# HB-OU-MP3-LED_V1_1.net
KiCad netlist of a schematic drawn in EAGLE
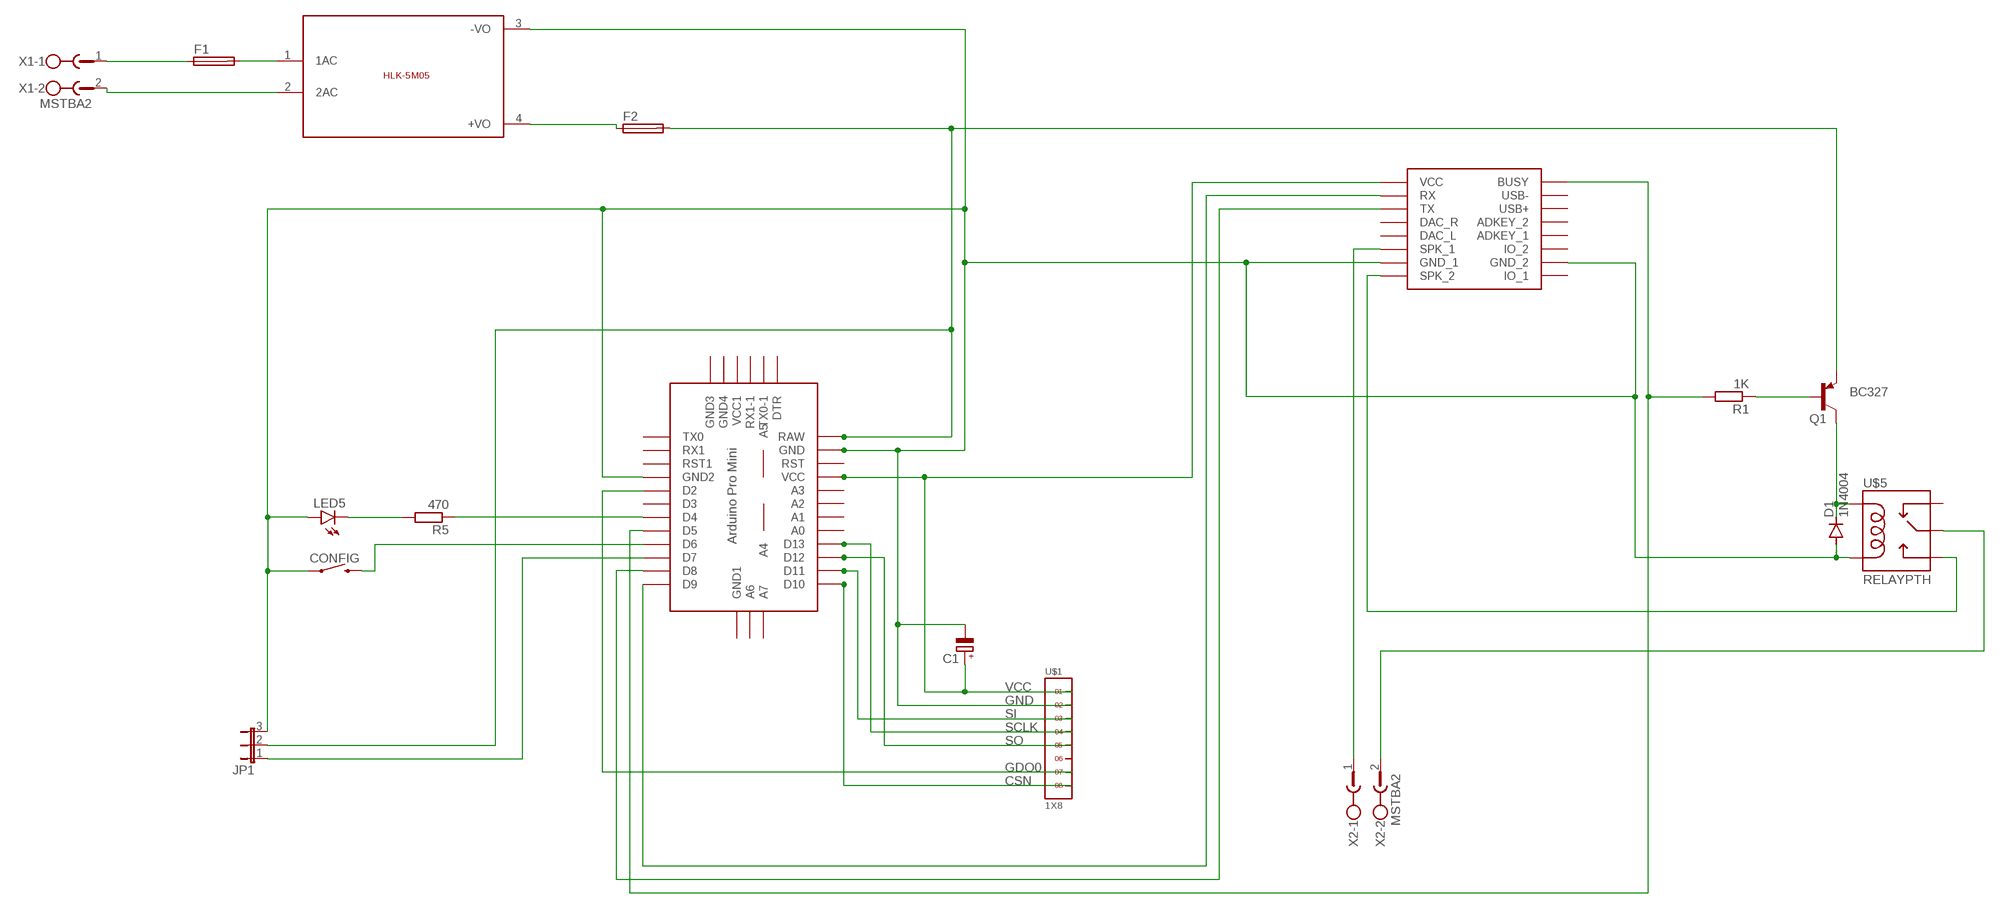
[diagram p0: schematic, sheet 1]

(export (version "E")
  (design (tool "Eeschema 10.0.6"))
  (components
    (comp (ref "C1")
      (value "CPOL-EUE2.5-5")
      (footprint "eagle-import:E2,5-5")
      (libsource (lib "eagle-import") (part "CPOL-EUE2.5-5"))
    )
    (comp (ref "CONFIG")
      (value "MOMENTARY-SWITCH-SPST-PTH-6.0MM-KIT")
      (footprint "eagle-import:TACTILE_SWITCH_PTH_6.0MM_KIT")
      (libsource (lib "eagle-import") (part "MOMENTARY-SWITCH-SPST-PTH-6.0MM-KIT"))
    )
    (comp (ref "D1")
      (value "1N4004")
      (footprint "eagle-import:DO41-10")
      (libsource (lib "eagle-import") (part "1N4004"))
    )
    (comp (ref "F1")
      (value "SH22,5A")
      (footprint "eagle-import:SH22,5A")
      (fields (field (name "MPN") "0031.7701.11"))
      (libsource (lib "eagle-import") (part "SH22,5A"))
    )
    (comp (ref "F2")
      (value "SH22,5A")
      (footprint "eagle-import:SH22,5A")
      (fields (field (name "MPN") "0031.7701.11"))
      (libsource (lib "eagle-import") (part "SH22,5A"))
    )
    (comp (ref "JP1")
      (value "JP2E")
      (footprint "eagle-import:JP2")
      (libsource (lib "eagle-import") (part "JP2E"))
    )
    (comp (ref "LED5")
      (value "LED3MM")
      (footprint "eagle-import:LED3MM")
      (libsource (lib "eagle-import") (part "LED3MM"))
    )
    (comp (ref "Q1")
      (value "BC327")
      (footprint "eagle-import:TO92")
      (libsource (lib "eagle-import") (part "BC327"))
    )
    (comp (ref "R1")
      (value "1K")
      (footprint "eagle-import:0309_10")
      (libsource (lib "eagle-import") (part "R-EU_0309/10"))
    )
    (comp (ref "R5")
      (value "470")
      (footprint "eagle-import:0309_10")
      (libsource (lib "eagle-import") (part "R-EU_0309/10"))
    )
    (comp (ref "U$1")
      (value "1X8")
      (footprint "eagle-import:1X8")
      (libsource (lib "eagle-import") (part "1X8"))
    )
    (comp (ref "U$2")
      (value "ABK-PRO-MINI")
      (footprint "eagle-import:ABK-PRO-MINI")
      (libsource (lib "eagle-import") (part "ABK-PRO-MINI"))
    )
    (comp (ref "U$3")
      (value "5VDC/5W")
      (footprint "eagle-import:HLK-5M05")
      (libsource (lib "eagle-import") (part "HLK-5M05"))
    )
    (comp (ref "U$4")
      (value "DFPLAYER")
      (footprint "eagle-import:DFPLAYER")
      (libsource (lib "eagle-import") (part "DFPLAYER"))
    )
    (comp (ref "U$5")
      (value "RELAYPTH")
      (footprint "eagle-import:SRD-05VDC-SL-C")
      (libsource (lib "eagle-import") (part "RELAYPTH"))
    )
    (comp (ref "X1")
      (value "MSTBA2")
      (footprint "eagle-import:MSTBA2")
      (fields (field (name "MF") "FARNELL") (field (name "MPN") "1757242"))
      (libsource (lib "eagle-import") (part "MSTBA2"))
    )
    (comp (ref "X2")
      (value "MSTBA2")
      (footprint "eagle-import:MSTBA2")
      (fields (field (name "MF") "FARNELL") (field (name "MPN") "1757242"))
      (libsource (lib "eagle-import") (part "MSTBA2"))
    )
  )
  (nets
    (net (code "1") (name "/CSN") (class "Default")
      (node (ref "U$1") (pin "8") (pinfunction "8_8") (pintype "bidirectional"))
      (node (ref "U$2") (pin "D10") (pinfunction "D10_D10") (pintype "bidirectional"))
    )
    (net (code "2") (name "/GDO0") (class "Default")
      (node (ref "U$1") (pin "7") (pinfunction "7_7") (pintype "bidirectional"))
      (node (ref "U$2") (pin "D2") (pinfunction "D2_D2") (pintype "bidirectional"))
    )
    (net (code "3") (name "/GND") (class "Default")
      (node (ref "C1") (pin "-") (pinfunction "-_-") (pintype "passive"))
      (node (ref "CONFIG") (pin "1") (pinfunction "1_1") (pintype "passive"))
      (node (ref "D1") (pin "A") (pinfunction "A_A") (pintype "passive"))
      (node (ref "JP1") (pin "3") (pinfunction "3_3") (pintype "passive"))
      (node (ref "LED5") (pin "A") (pinfunction "A_A") (pintype "passive"))
      (node (ref "U$1") (pin "2") (pinfunction "2_2") (pintype "bidirectional"))
      (node (ref "U$2") (pin "GND") (pinfunction "GND_GND") (pintype "bidirectional"))
      (node (ref "U$2") (pin "GND1") (pinfunction "GND2_GND1") (pintype "bidirectional"))
      (node (ref "U$3") (pin "3") (pinfunction "-VO_3") (pintype "bidirectional"))
      (node (ref "U$4") (pin "GND_1") (pinfunction "GND_1_GND_1") (pintype "bidirectional"))
      (node (ref "U$4") (pin "GND_2") (pinfunction "GND_2_GND_2") (pintype "bidirectional"))
      (node (ref "U$5") (pin "COIL0") (pinfunction "COIL0_COIL0") (pintype "bidirectional"))
    )
    (net (code "4") (name "/SCLK") (class "Default")
      (node (ref "U$1") (pin "4") (pinfunction "4_4") (pintype "bidirectional"))
      (node (ref "U$2") (pin "D13") (pinfunction "D13_D13") (pintype "bidirectional"))
    )
    (net (code "5") (name "/SI") (class "Default")
      (node (ref "U$1") (pin "3") (pinfunction "3_3") (pintype "bidirectional"))
      (node (ref "U$2") (pin "D11") (pinfunction "D11_D11") (pintype "bidirectional"))
    )
    (net (code "6") (name "/SO") (class "Default")
      (node (ref "U$1") (pin "5") (pinfunction "5_5") (pintype "bidirectional"))
      (node (ref "U$2") (pin "D12") (pinfunction "D12_D12") (pintype "bidirectional"))
    )
    (net (code "7") (name "/VCC") (class "Default")
      (node (ref "C1") (pin "+") (pinfunction "+_+") (pintype "passive"))
      (node (ref "U$1") (pin "1") (pinfunction "1_1") (pintype "bidirectional"))
      (node (ref "U$2") (pin "VCC") (pinfunction "VCC_VCC") (pintype "bidirectional"))
      (node (ref "U$4") (pin "VCC") (pinfunction "VCC_VCC") (pintype "bidirectional"))
    )
    (net (code "8") (name "Net-(CONFIG-2)") (class "Default")
      (node (ref "CONFIG") (pin "3") (pinfunction "2_3") (pintype "passive"))
      (node (ref "U$2") (pin "D6") (pinfunction "D6_D6") (pintype "bidirectional"))
    )
    (net (code "9") (name "Net-(F1-Pad1)") (class "Default")
      (node (ref "F1") (pin "1") (pinfunction "1_1") (pintype "passive"))
      (node (ref "X1") (pin "1") (pinfunction "1_1") (pintype "passive"))
    )
    (net (code "10") (name "Net-(JP1-Pad1)") (class "Default")
      (node (ref "JP1") (pin "1") (pinfunction "1_1") (pintype "passive"))
      (node (ref "U$2") (pin "D7") (pinfunction "D7_D7") (pintype "bidirectional"))
    )
    (net (code "11") (name "Net-(LED5-C)") (class "Default")
      (node (ref "LED5") (pin "K") (pinfunction "C_K") (pintype "passive"))
      (node (ref "R5") (pin "2") (pinfunction "2_2") (pintype "passive"))
    )
    (net (code "12") (name "Net-(Q1-B)") (class "Default")
      (node (ref "Q1") (pin "2") (pinfunction "B_2") (pintype "passive"))
      (node (ref "R1") (pin "1") (pinfunction "1_1") (pintype "passive"))
    )
    (net (code "13") (name "Net-(Q1-C)") (class "Default")
      (node (ref "D1") (pin "C") (pinfunction "C_C") (pintype "passive"))
      (node (ref "Q1") (pin "3") (pinfunction "C_3") (pintype "passive"))
      (node (ref "U$5") (pin "COIL1") (pinfunction "COIL1_COIL1") (pintype "bidirectional"))
    )
    (net (code "14") (name "Net-(Q1-E)") (class "Default")
      (node (ref "F2") (pin "2") (pinfunction "2_2") (pintype "passive"))
      (node (ref "JP1") (pin "2") (pinfunction "2_2") (pintype "passive"))
      (node (ref "Q1") (pin "1") (pinfunction "E_1") (pintype "passive"))
      (node (ref "U$2") (pin "RAW") (pinfunction "RAW_RAW") (pintype "bidirectional"))
    )
    (net (code "15") (name "Net-(R1-Pad2)") (class "Default")
      (node (ref "R1") (pin "2") (pinfunction "2_2") (pintype "passive"))
      (node (ref "U$2") (pin "D5") (pinfunction "D5_D5") (pintype "bidirectional"))
      (node (ref "U$4") (pin "BUSY") (pinfunction "BUSY_BUSY") (pintype "bidirectional"))
    )
    (net (code "16") (name "Net-(R5-Pad1)") (class "Default")
      (node (ref "R5") (pin "1") (pinfunction "1_1") (pintype "passive"))
      (node (ref "U$2") (pin "D4") (pinfunction "D4_D4") (pintype "bidirectional"))
    )
    (net (code "17") (name "Net-(U$2-PadD8)") (class "Default")
      (node (ref "U$2") (pin "D8") (pinfunction "D8_D8") (pintype "bidirectional"))
      (node (ref "U$4") (pin "TX") (pinfunction "TX_TX") (pintype "bidirectional"))
    )
    (net (code "18") (name "Net-(U$2-PadD9)") (class "Default")
      (node (ref "U$2") (pin "D9") (pinfunction "D9_D9") (pintype "bidirectional"))
      (node (ref "U$4") (pin "RX") (pinfunction "RX_RX") (pintype "bidirectional"))
    )
    (net (code "19") (name "Net-(U$3-+VO)") (class "Default")
      (node (ref "F2") (pin "1") (pinfunction "1_1") (pintype "passive"))
      (node (ref "U$3") (pin "4") (pinfunction "+VO_4") (pintype "bidirectional"))
    )
    (net (code "20") (name "Net-(U$3-1AC)") (class "Default")
      (node (ref "F1") (pin "2") (pinfunction "2_2") (pintype "passive"))
      (node (ref "U$3") (pin "1") (pinfunction "1AC_1") (pintype "bidirectional"))
    )
    (net (code "21") (name "Net-(U$3-2AC)") (class "Default")
      (node (ref "U$3") (pin "2") (pinfunction "2AC_2") (pintype "bidirectional"))
      (node (ref "X1") (pin "2") (pinfunction "1_2") (pintype "passive"))
    )
    (net (code "22") (name "Net-(U$4-SPK_1)") (class "Default")
      (node (ref "U$4") (pin "SPK1") (pinfunction "SPK_1_SPK1") (pintype "bidirectional"))
      (node (ref "X2") (pin "1") (pinfunction "1_1") (pintype "passive"))
    )
    (net (code "23") (name "Net-(U$4-SPK_2)") (class "Default")
      (node (ref "U$4") (pin "SPK2") (pinfunction "SPK_2_SPK2") (pintype "bidirectional"))
      (node (ref "U$5") (pin "SWOPEN") (pinfunction "SWOPEN_SWOPEN") (pintype "bidirectional"))
    )
    (net (code "24") (name "Net-(X2B-1)") (class "Default")
      (node (ref "U$5") (pin "SWCOMMON") (pinfunction "SWCOMMON_SWCOMMON") (pintype "bidirectional"))
      (node (ref "X2") (pin "2") (pinfunction "1_2") (pintype "passive"))
    )
    (net (code "25") (name "unconnected-(U$1-Pad6)") (class "Default")
      (node (ref "U$1") (pin "6") (pinfunction "6_6") (pintype "bidirectional"))
    )
    (net (code "26") (name "unconnected-(U$2-GND1-PadGND4)") (class "Default")
      (node (ref "U$2") (pin "GND4") (pinfunction "GND1_GND4") (pintype "bidirectional"))
    )
    (net (code "27") (name "unconnected-(U$2-GND3-PadGND2)") (class "Default")
      (node (ref "U$2") (pin "GND2") (pinfunction "GND3_GND2") (pintype "bidirectional"))
    )
    (net (code "28") (name "unconnected-(U$2-GND4-PadGND3)") (class "Default")
      (node (ref "U$2") (pin "GND3") (pinfunction "GND4_GND3") (pintype "bidirectional"))
    )
    (net (code "29") (name "unconnected-(U$2-PadA0)") (class "Default")
      (node (ref "U$2") (pin "A0") (pinfunction "A0_A0") (pintype "bidirectional"))
    )
    (net (code "30") (name "unconnected-(U$2-PadA1)") (class "Default")
      (node (ref "U$2") (pin "A1") (pinfunction "A1_A1") (pintype "bidirectional"))
    )
    (net (code "31") (name "unconnected-(U$2-PadA2)") (class "Default")
      (node (ref "U$2") (pin "A2") (pinfunction "A2_A2") (pintype "bidirectional"))
    )
    (net (code "32") (name "unconnected-(U$2-PadA3)") (class "Default")
      (node (ref "U$2") (pin "A3") (pinfunction "A3_A3") (pintype "bidirectional"))
    )
    (net (code "33") (name "unconnected-(U$2-PadA4)") (class "Default")
      (node (ref "U$2") (pin "A4") (pinfunction "A4_A4") (pintype "bidirectional"))
    )
    (net (code "34") (name "unconnected-(U$2-PadA5)") (class "Default")
      (node (ref "U$2") (pin "A5") (pinfunction "A5_A5") (pintype "bidirectional"))
    )
    (net (code "35") (name "unconnected-(U$2-PadA6)") (class "Default")
      (node (ref "U$2") (pin "A6") (pinfunction "A6_A6") (pintype "bidirectional"))
    )
    (net (code "36") (name "unconnected-(U$2-PadA7)") (class "Default")
      (node (ref "U$2") (pin "A7") (pinfunction "A7_A7") (pintype "bidirectional"))
    )
    (net (code "37") (name "unconnected-(U$2-PadD3)") (class "Default")
      (node (ref "U$2") (pin "D3") (pinfunction "D3_D3") (pintype "bidirectional"))
    )
    (net (code "38") (name "unconnected-(U$2-PadDTR)") (class "Default")
      (node (ref "U$2") (pin "DTR") (pinfunction "DTR_DTR") (pintype "bidirectional"))
    )
    (net (code "39") (name "unconnected-(U$2-PadRST)") (class "Default")
      (node (ref "U$2") (pin "RST") (pinfunction "RST_RST") (pintype "bidirectional"))
    )
    (net (code "40") (name "unconnected-(U$2-PadRST1)") (class "Default")
      (node (ref "U$2") (pin "RST1") (pinfunction "RST1_RST1") (pintype "bidirectional"))
    )
    (net (code "41") (name "unconnected-(U$2-PadRX1)") (class "Default")
      (node (ref "U$2") (pin "RX1") (pinfunction "RX1_RX1") (pintype "bidirectional"))
    )
    (net (code "42") (name "unconnected-(U$2-PadRX1-1)") (class "Default")
      (node (ref "U$2") (pin "RX1-1") (pinfunction "RX1-1_RX1-1") (pintype "bidirectional"))
    )
    (net (code "43") (name "unconnected-(U$2-PadTX0)") (class "Default")
      (node (ref "U$2") (pin "TX0") (pinfunction "TX0_TX0") (pintype "bidirectional"))
    )
    (net (code "44") (name "unconnected-(U$2-PadTX0-1)") (class "Default")
      (node (ref "U$2") (pin "TX0-1") (pinfunction "TX0-1_TX0-1") (pintype "bidirectional"))
    )
    (net (code "45") (name "unconnected-(U$2-PadVCC1)") (class "Default")
      (node (ref "U$2") (pin "VCC1") (pinfunction "VCC1_VCC1") (pintype "bidirectional"))
    )
    (net (code "46") (name "unconnected-(U$4-ADKEY_1-PadADKEY1)") (class "Default")
      (node (ref "U$4") (pin "ADKEY1") (pinfunction "ADKEY_1_ADKEY1") (pintype "bidirectional"))
    )
    (net (code "47") (name "unconnected-(U$4-ADKEY_2-PadADKEY2)") (class "Default")
      (node (ref "U$4") (pin "ADKEY2") (pinfunction "ADKEY_2_ADKEY2") (pintype "bidirectional"))
    )
    (net (code "48") (name "unconnected-(U$4-IO_1-PadIO1)") (class "Default")
      (node (ref "U$4") (pin "IO1") (pinfunction "IO_1_IO1") (pintype "bidirectional"))
    )
    (net (code "49") (name "unconnected-(U$4-IO_2-PadIO2)") (class "Default")
      (node (ref "U$4") (pin "IO2") (pinfunction "IO_2_IO2") (pintype "bidirectional"))
    )
    (net (code "50") (name "unconnected-(U$4-PadDAC_L)") (class "Default")
      (node (ref "U$4") (pin "DAC_L") (pinfunction "DAC_L_DAC_L") (pintype "bidirectional"))
    )
    (net (code "51") (name "unconnected-(U$4-PadDAC_R)") (class "Default")
      (node (ref "U$4") (pin "DAC_R") (pinfunction "DAC_R_DAC_R") (pintype "bidirectional"))
    )
    (net (code "52") (name "unconnected-(U$4-PadUSB+)") (class "Default")
      (node (ref "U$4") (pin "USB+") (pinfunction "USB+_USB+") (pintype "bidirectional"))
    )
    (net (code "53") (name "unconnected-(U$4-PadUSB-)") (class "Default")
      (node (ref "U$4") (pin "USB-") (pinfunction "USB-_USB-") (pintype "bidirectional"))
    )
    (net (code "54") (name "unconnected-(U$5-SWCLOSE-PadSWCLOSED)") (class "Default")
      (node (ref "U$5") (pin "SWCLOSED") (pinfunction "SWCLOSE_SWCLOSED") (pintype "bidirectional"))
    )
  )
)
